# Encoder.net
KiCad netlist of a schematic drawn in Altium Designer
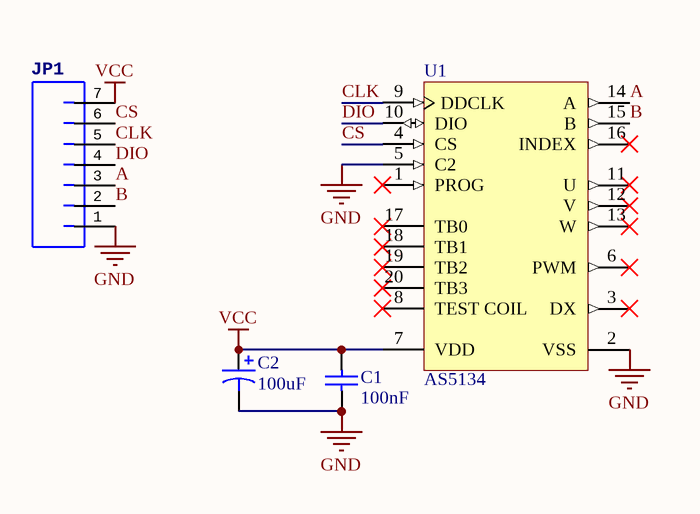
[diagram p0: Encoder.SchDoc]

(export (version "E")
  (design (tool "Eeschema 10.0.6"))
  (components
    (comp (ref "C1")
      (value "100nF")
      (footprint "CAPC0603(1608)100_N")
      (description "CAP 100nF 6.3V Â±5% 0603 (1608 Metric) Thickness 1mm SMD")
      (fields (field (name "TOLERANCE") "Â±5%"))
      (libsource (lib "Altium Content Vault") (part "CMP-1035-02575-1"))
    )
    (comp (ref "C2")
      (value "100uF")
      (footprint "AVX-CAPC7343_V")
      (libsource (lib "Components") (part "AVX-CAP-P-2"))
    )
    (comp (ref "JP1") (value "~") (footprint "JST-7-PTH") (libsource (lib "Components") (part "JST_7_RIGHT")))
    (comp (ref "U1")
      (value "AS5134")
      (footprint "AMS-SSOP-20-7200X5300DE_M")
      (description "360 Step Programmable High Speed Magnetic Rotary Encoder, 5 V, SSOP-20, Pb-Free, Reel")
      (fields (field (name "PARTNUMBER") "AS5134-ZSST") (field (name "MANUFACTURER") "AMS"))
      (libsource (lib "Altium Content Vault") (part "CMP-0555-00029-2"))
    )
  )
  (nets
    (net (code "1") (name "/A") (class "Default")
      (node (ref "JP1") (pin "3") (pinfunction "3_3") (pintype "passive"))
      (node (ref "U1") (pin "14") (pinfunction "A_14") (pintype "output"))
    )
    (net (code "2") (name "/B") (class "Default")
      (node (ref "JP1") (pin "2") (pinfunction "2_2") (pintype "passive"))
      (node (ref "U1") (pin "15") (pinfunction "B_15") (pintype "output"))
    )
    (net (code "3") (name "/CLK") (class "Default")
      (node (ref "JP1") (pin "5") (pinfunction "5_5") (pintype "passive"))
      (node (ref "U1") (pin "9") (pinfunction "DDCLK_9") (pintype "input"))
    )
    (net (code "4") (name "/CS") (class "Default")
      (node (ref "JP1") (pin "6") (pinfunction "6_6") (pintype "passive"))
      (node (ref "U1") (pin "4") (pinfunction "CS_4") (pintype "input"))
    )
    (net (code "5") (name "/DIO") (class "Default")
      (node (ref "JP1") (pin "4") (pinfunction "4_4") (pintype "passive"))
      (node (ref "U1") (pin "10") (pinfunction "DIO_10") (pintype "bidirectional"))
    )
    (net (code "6") (name "GND") (class "Default")
      (node (ref "C1") (pin "1") (pinfunction "1_1") (pintype "passive"))
      (node (ref "C2") (pin "2") (pinfunction "2_2") (pintype "passive"))
      (node (ref "JP1") (pin "1") (pinfunction "1_1") (pintype "passive"))
      (node (ref "U1") (pin "2") (pinfunction "VSS_2") (pintype "power_in"))
      (node (ref "U1") (pin "5") (pinfunction "C2_5") (pintype "input"))
    )
    (net (code "7") (name "VCC") (class "Default")
      (node (ref "C1") (pin "2") (pinfunction "2_2") (pintype "passive"))
      (node (ref "C2") (pin "1") (pinfunction "1_1") (pintype "passive"))
      (node (ref "JP1") (pin "7") (pinfunction "7_7") (pintype "passive"))
      (node (ref "U1") (pin "7") (pinfunction "VDD_7") (pintype "power_in"))
    )
    (net (code "8") (name "unconnected-(U1-DX-Pad3)") (class "Default")
      (node (ref "U1") (pin "3") (pinfunction "DX_3") (pintype "output+no_connect"))
    )
    (net (code "9") (name "unconnected-(U1-INDEX-Pad16)") (class "Default")
      (node (ref "U1") (pin "16") (pinfunction "INDEX_16") (pintype "output+no_connect"))
    )
    (net (code "10") (name "unconnected-(U1-PROG-Pad1)") (class "Default")
      (node (ref "U1") (pin "1") (pinfunction "PROG_1") (pintype "input+no_connect"))
    )
    (net (code "11") (name "unconnected-(U1-PWM-Pad6)") (class "Default")
      (node (ref "U1") (pin "6") (pinfunction "PWM_6") (pintype "output+no_connect"))
    )
    (net (code "12") (name "unconnected-(U1-TB0-Pad17)") (class "Default")
      (node (ref "U1") (pin "17") (pinfunction "TB0_17") (pintype "passive+no_connect"))
    )
    (net (code "13") (name "unconnected-(U1-TB1-Pad18)") (class "Default")
      (node (ref "U1") (pin "18") (pinfunction "TB1_18") (pintype "passive+no_connect"))
    )
    (net (code "14") (name "unconnected-(U1-TB2-Pad19)") (class "Default")
      (node (ref "U1") (pin "19") (pinfunction "TB2_19") (pintype "passive+no_connect"))
    )
    (net (code "15") (name "unconnected-(U1-TB3-Pad20)") (class "Default")
      (node (ref "U1") (pin "20") (pinfunction "TB3_20") (pintype "passive+no_connect"))
    )
    (net (code "16") (name "unconnected-(U1-TEST_COIL-Pad8)") (class "Default")
      (node (ref "U1") (pin "8") (pinfunction "TEST_COIL_8") (pintype "passive+no_connect"))
    )
    (net (code "17") (name "unconnected-(U1-U-Pad11)") (class "Default")
      (node (ref "U1") (pin "11") (pinfunction "U_11") (pintype "output+no_connect"))
    )
    (net (code "18") (name "unconnected-(U1-V-Pad12)") (class "Default")
      (node (ref "U1") (pin "12") (pinfunction "V_12") (pintype "output+no_connect"))
    )
    (net (code "19") (name "unconnected-(U1-W-Pad13)") (class "Default")
      (node (ref "U1") (pin "13") (pinfunction "W_13") (pintype "output+no_connect"))
    )
  )
)
